# Main_Roll.net
KiCad netlist of a schematic drawn in Altium Designer
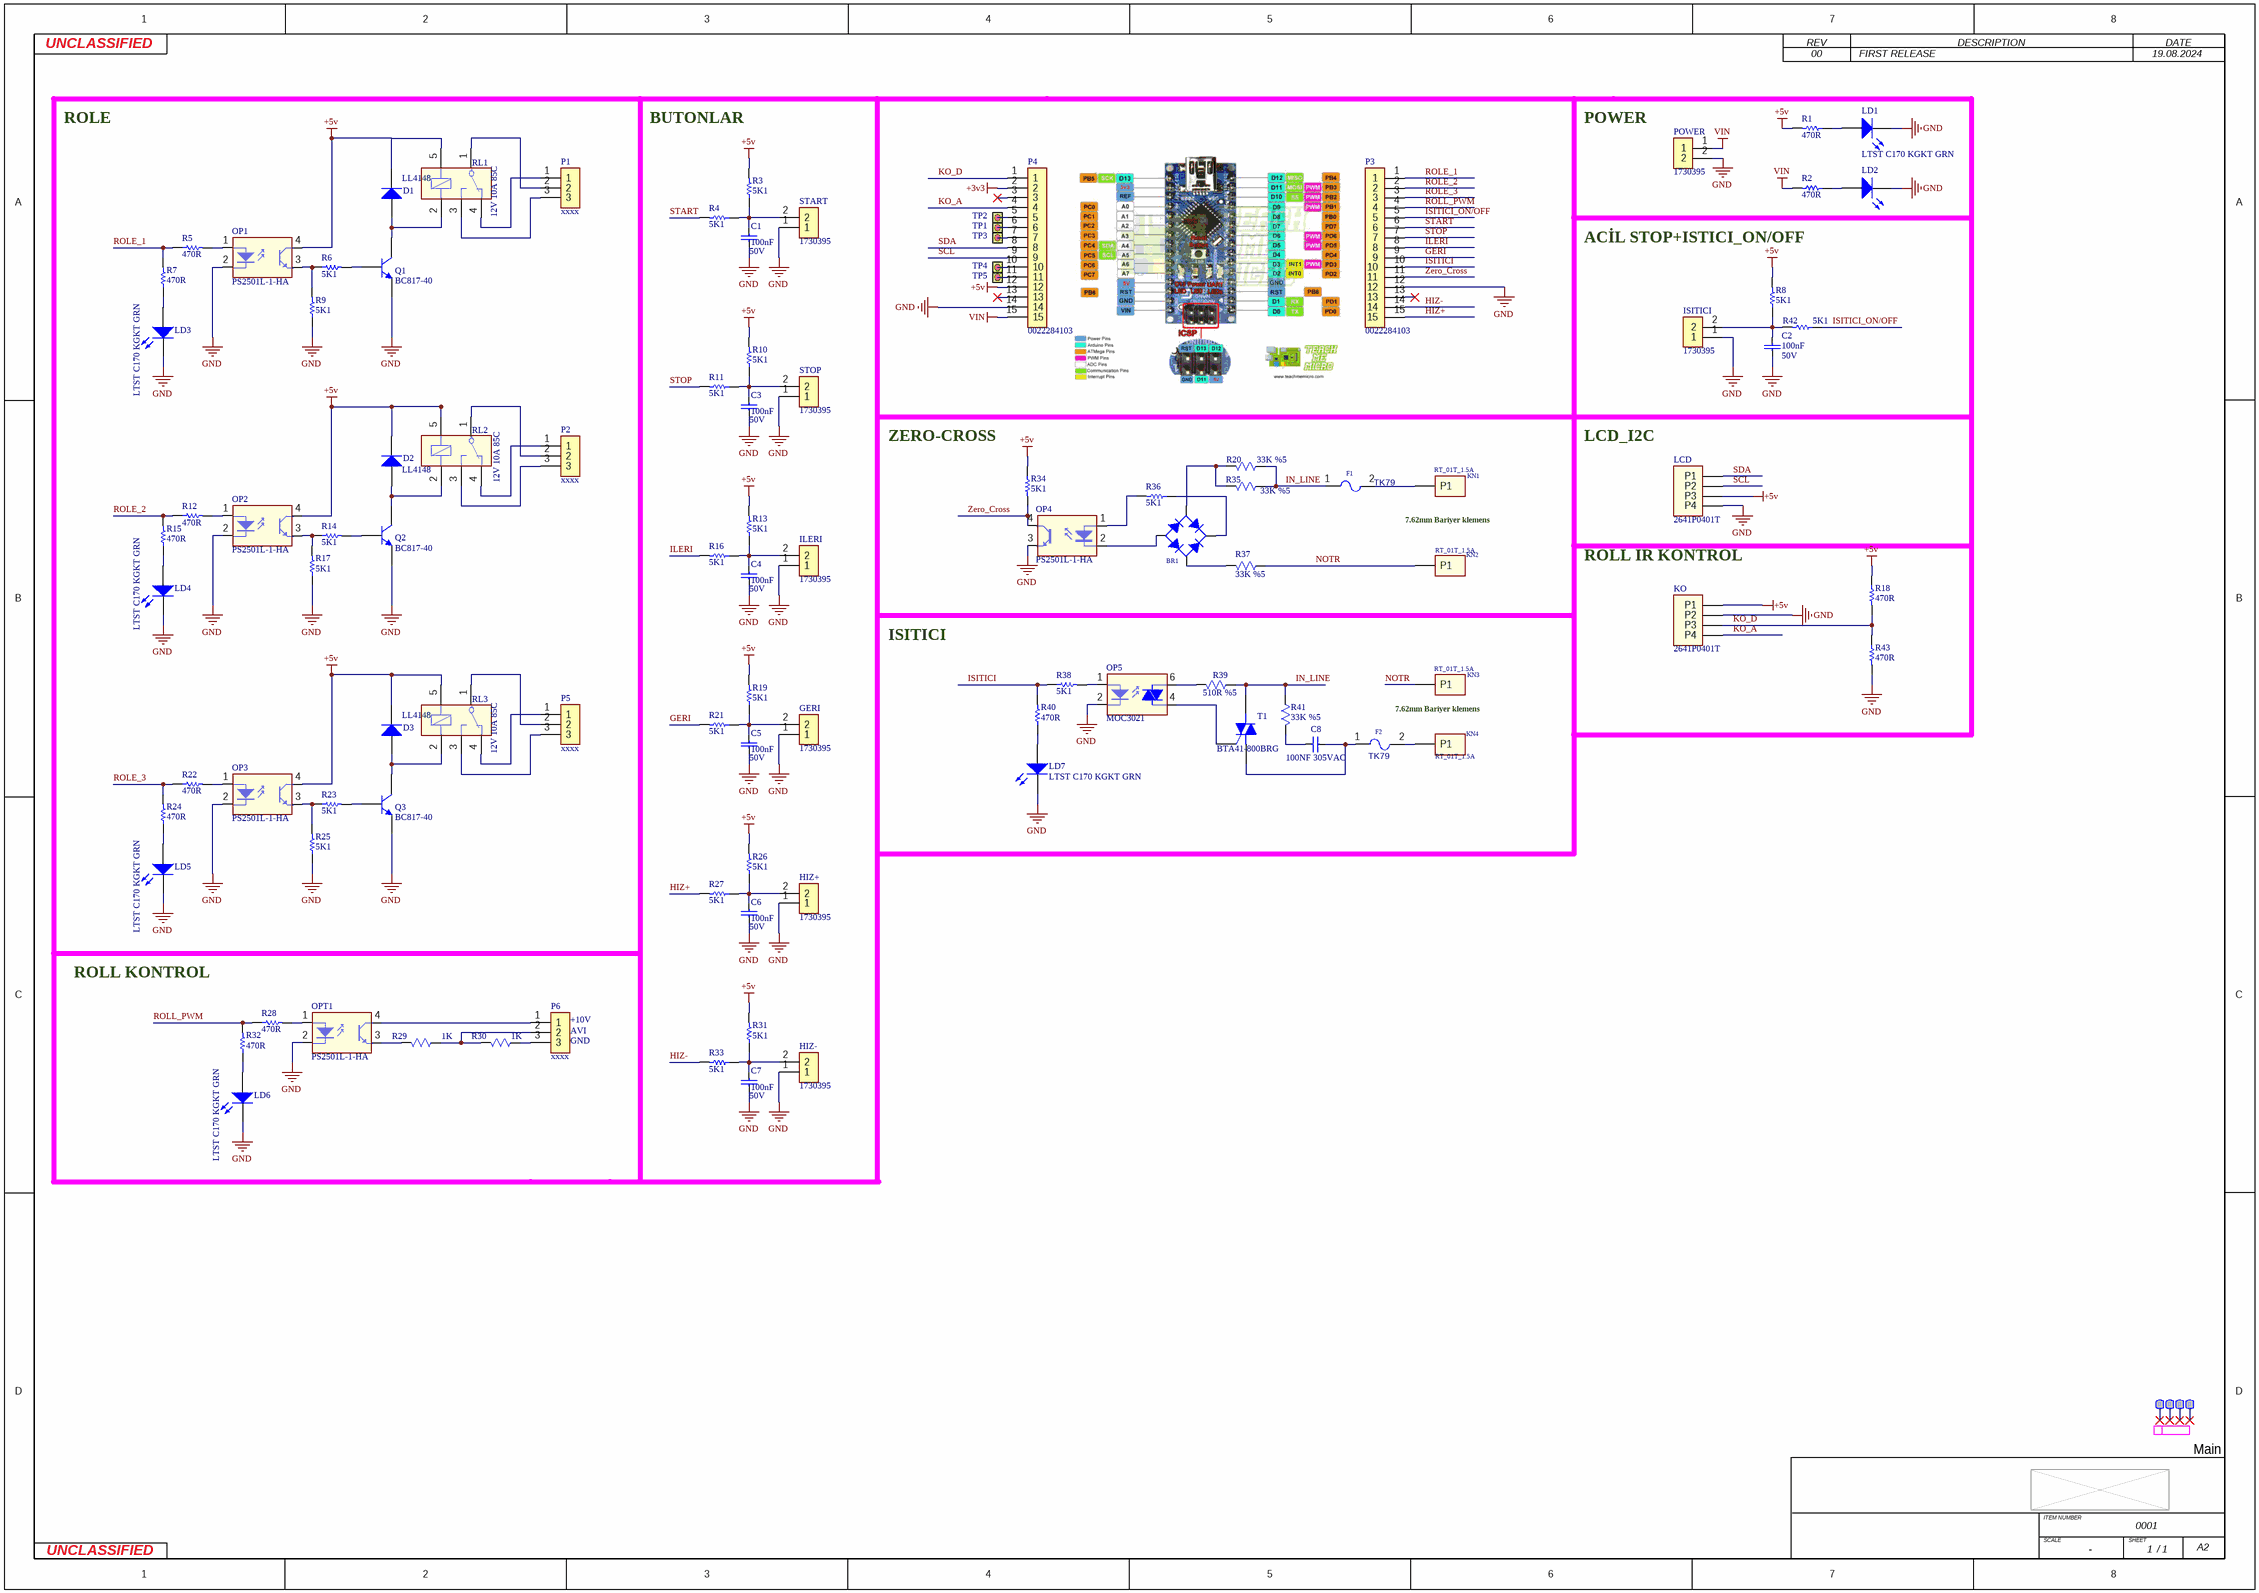
[diagram p0: Main_Roll.SchDoc]

(export (version "E")
  (design (tool "Eeschema 10.0.6"))
  (components
    (comp (ref "BR1")
      (value "~")
      (footprint "TO-269AA")
      (fields (field (name "PART NUMBER") "MB6S"))
      (libsource (lib "A_LIB") (part "B250D"))
    )
    (comp (ref "C1")
      (value "100nF")
      (footprint "C1206")
      (description "CAPACITOR, CERAMIC, 100nF, 50V, 10% TOLERANCE, X7R, 1206 PACKAGE")
      (fields
        (field (name "INITIAL VOLTAGE") "50V")
        (field (name "MANUFACTURER") "AVX")
        (field (name "TOLERANCE") "10%")
      )
      (libsource (lib "R_DB_LIB") (part "CAP"))
    )
    (comp (ref "C2")
      (value "100nF")
      (footprint "C1206")
      (description "CAPACITOR, CERAMIC, 100nF, 50V, 10% TOLERANCE, X7R, 1206 PACKAGE")
      (fields
        (field (name "INITIAL VOLTAGE") "50V")
        (field (name "MANUFACTURER") "AVX")
        (field (name "TOLERANCE") "10%")
      )
      (libsource (lib "R_DB_LIB") (part "CAP"))
    )
    (comp (ref "C3")
      (value "100nF")
      (footprint "C1206")
      (description "CAPACITOR, CERAMIC, 100nF, 50V, 10% TOLERANCE, X7R, 1206 PACKAGE")
      (fields
        (field (name "INITIAL VOLTAGE") "50V")
        (field (name "MANUFACTURER") "AVX")
        (field (name "TOLERANCE") "10%")
      )
      (libsource (lib "R_DB_LIB") (part "CAP"))
    )
    (comp (ref "C4")
      (value "100nF")
      (footprint "C1206")
      (description "CAPACITOR, CERAMIC, 100nF, 50V, 10% TOLERANCE, X7R, 1206 PACKAGE")
      (fields
        (field (name "INITIAL VOLTAGE") "50V")
        (field (name "MANUFACTURER") "AVX")
        (field (name "TOLERANCE") "10%")
      )
      (libsource (lib "R_DB_LIB") (part "CAP"))
    )
    (comp (ref "C5")
      (value "100nF")
      (footprint "C1206")
      (description "CAPACITOR, CERAMIC, 100nF, 50V, 10% TOLERANCE, X7R, 1206 PACKAGE")
      (fields
        (field (name "INITIAL VOLTAGE") "50V")
        (field (name "MANUFACTURER") "AVX")
        (field (name "TOLERANCE") "10%")
      )
      (libsource (lib "R_DB_LIB") (part "CAP"))
    )
    (comp (ref "C6")
      (value "100nF")
      (footprint "C1206")
      (description "CAPACITOR, CERAMIC, 100nF, 50V, 10% TOLERANCE, X7R, 1206 PACKAGE")
      (fields
        (field (name "INITIAL VOLTAGE") "50V")
        (field (name "MANUFACTURER") "AVX")
        (field (name "TOLERANCE") "10%")
      )
      (libsource (lib "R_DB_LIB") (part "CAP"))
    )
    (comp (ref "C7")
      (value "100nF")
      (footprint "C1206")
      (description "CAPACITOR, CERAMIC, 100nF, 50V, 10% TOLERANCE, X7R, 1206 PACKAGE")
      (fields
        (field (name "INITIAL VOLTAGE") "50V")
        (field (name "MANUFACTURER") "AVX")
        (field (name "TOLERANCE") "10%")
      )
      (libsource (lib "R_DB_LIB") (part "CAP"))
    )
    (comp (ref "C8")
      (value "100NF 305VAC")
      (footprint "CFR F15 L18 B6 H12")
      (fields (field (name "PART NUMBER") "CFR15 100NF 305VAC M85 X2"))
      (libsource (lib "A_LIB") (part "Capacitor"))
    )
    (comp (ref "D1")
      (value "LL4148")
      (footprint "SOD80")
      (fields (field (name "PART NUMBER") "1N4148-S"))
      (libsource (lib "A_LIB") (part "Diode"))
    )
    (comp (ref "D2")
      (value "LL4148")
      (footprint "SOD80")
      (fields (field (name "PART NUMBER") "1N4148-S"))
      (libsource (lib "") (part "Diode_1"))
    )
    (comp (ref "D3")
      (value "LL4148")
      (footprint "SOD80")
      (fields (field (name "PART NUMBER") "1N4148-S"))
      (libsource (lib "A_LIB") (part "Diode"))
    )
    (comp (ref "ETİKET1") (value "Etiket") (footprint "ETIKET") (libsource (lib "R_DB_LIB") (part "Etiket")))
    (comp (ref "F1")
      (value "TK79")
      (footprint "TK 79")
      (fields (field (name "PART NUMBER") "FUSE TK79"))
      (libsource (lib "A_LIB") (part "Fuse"))
    )
    (comp (ref "F2")
      (value "TK79")
      (footprint "TK 79")
      (fields (field (name "PART NUMBER") "FUSE TK79"))
      (libsource (lib "") (part "Fuse_1"))
    )
    (comp (ref "GERI")
      (value "1730395")
      (footprint "1730395")
      (description "CONN,RECT,PLUG,5.08MM,1ROW,2P-TH,1730395")
      (fields (field (name "MANUFACTURER") "PHONEIX CONTACT"))
      (libsource (lib "") (part "HDR1X2_1"))
    )
    (comp (ref "HIZ+")
      (value "1730395")
      (footprint "1730395")
      (description "CONN,RECT,PLUG,5.08MM,1ROW,2P-TH,1730395")
      (fields (field (name "MANUFACTURER") "PHONEIX CONTACT"))
      (libsource (lib "") (part "HDR1X2_1"))
    )
    (comp (ref "HIZ-")
      (value "1730395")
      (footprint "1730395")
      (description "CONN,RECT,PLUG,5.08MM,1ROW,2P-TH,1730395")
      (fields (field (name "MANUFACTURER") "PHONEIX CONTACT"))
      (libsource (lib "") (part "HDR1X2_1"))
    )
    (comp (ref "ILERI")
      (value "1730395")
      (footprint "1730395")
      (description "CONN,RECT,PLUG,5.08MM,1ROW,2P-TH,1730395")
      (fields (field (name "MANUFACTURER") "PHONEIX CONTACT"))
      (libsource (lib "") (part "HDR1X2_1"))
    )
    (comp (ref "ISITICI")
      (value "1730395")
      (footprint "1730395")
      (description "CONN,RECT,PLUG,5.08MM,1ROW,2P-TH,1730395")
      (fields (field (name "MANUFACTURER") "PHONEIX CONTACT"))
      (libsource (lib "R_DB_LIB") (part "HDR1X2"))
    )
    (comp (ref "KN1")
      (value "RT_01T_1.5A")
      (footprint "RT_01T_1.5A")
      (libsource (lib "A_LIB") (part "CONN 1_1"))
    )
    (comp (ref "KN2")
      (value "RT_01T_1.5A")
      (footprint "RT_01T_1.5A")
      (libsource (lib "A_LIB") (part "CONN 1_1"))
    )
    (comp (ref "KN3")
      (value "RT_01T_1.5A")
      (footprint "RT_01T_1.5A")
      (libsource (lib "A_LIB") (part "CONN 1_1"))
    )
    (comp (ref "KN4")
      (value "RT_01T_1.5A")
      (footprint "RT_01T_1.5A")
      (libsource (lib "A_LIB") (part "CONN 1_1"))
    )
    (comp (ref "KO") (value "2641P0401T") (footprint "35312_4") (libsource (lib "A_LIB") (part "CONN 4")))
    (comp (ref "LCD") (value "2641P0401T") (footprint "35312_4") (libsource (lib "A_LIB") (part "CONN 4")))
    (comp (ref "LD1")
      (value "LTST C170 KGKT GRN")
      (footprint "LED0805 GRN")
      (libsource (lib "A_LIB") (part "LED"))
    )
    (comp (ref "LD2")
      (value "LTST C170 KGKT GRN")
      (footprint "LED0805 GRN")
      (libsource (lib "A_LIB") (part "LED"))
    )
    (comp (ref "LD3")
      (value "LTST C170 KGKT GRN")
      (footprint "LED0805 GRN")
      (libsource (lib "A_LIB") (part "LED"))
    )
    (comp (ref "LD4")
      (value "LTST C170 KGKT GRN")
      (footprint "LED0805 GRN")
      (libsource (lib "A_LIB") (part "LED"))
    )
    (comp (ref "LD5")
      (value "LTST C170 KGKT GRN")
      (footprint "LED0805 GRN")
      (libsource (lib "A_LIB") (part "LED"))
    )
    (comp (ref "LD6")
      (value "LTST C170 KGKT GRN")
      (footprint "LED0805 GRN")
      (libsource (lib "A_LIB") (part "LED"))
    )
    (comp (ref "LD7")
      (value "LTST C170 KGKT GRN")
      (footprint "LED0805 GRN")
      (libsource (lib "") (part "LED_1"))
    )
    (comp (ref "OP1")
      (value "PS2501L-1-HA")
      (footprint "DIP4SMD")
      (fields (field (name "PART NUMBER") "PS2501-1-H"))
      (libsource (lib "") (part "Optocoupler(AKEC)_1"))
    )
    (comp (ref "OP2")
      (value "PS2501L-1-HA")
      (footprint "DIP4SMD")
      (fields (field (name "PART NUMBER") "PS2501-1-H"))
      (libsource (lib "") (part "Optocoupler(AKEC)_1"))
    )
    (comp (ref "OP3")
      (value "PS2501L-1-HA")
      (footprint "DIP4SMD")
      (fields (field (name "PART NUMBER") "PS2501-1-H"))
      (libsource (lib "") (part "Optocoupler(AKEC)_1"))
    )
    (comp (ref "OP4")
      (value "PS2501L-1-HA")
      (footprint "DIP4SMD")
      (fields (field (name "PART NUMBER") "PS2501-1-H"))
      (libsource (lib "A_LIB") (part "Optocoupler(AKEC)"))
    )
    (comp (ref "OP5") (value "MOC3021") (footprint "DIP6") (libsource (lib "A_LIB") (part "Optotriac")))
    (comp (ref "OPT1")
      (value "PS2501L-1-HA")
      (footprint "DIP4SMD")
      (fields (field (name "PART NUMBER") "PS2501-1-H"))
      (libsource (lib "") (part "Optocoupler(AKEC)_1"))
    )
    (comp (ref "P1")
      (value "xxxx")
      (footprint "5.08_3pin")
      (description "CONN,RECT,PLUG,5.08MM,1ROW,3P-TH,xxx")
      (fields (field (name "MANUFACTURER") "PHONEIX CONTACT"))
      (libsource (lib "R_DB_LIB") (part "HDR1X3"))
    )
    (comp (ref "P2")
      (value "xxxx")
      (footprint "5.08_3pin")
      (description "CONN,RECT,PLUG,5.08MM,1ROW,3P-TH,xxx")
      (fields (field (name "MANUFACTURER") "PHONEIX CONTACT"))
      (libsource (lib "R_DB_LIB") (part "HDR1X3"))
    )
    (comp (ref "P3")
      (value "0022284103")
      (footprint "HDR1X15")
      (description "CONN, 2.54MM PITCH, THROUGH HOLE, SINGLE ROW, VERTICAL, 15 PIN, PIN,")
      (fields
        (field (name "MANUFACTURER") "MOLEX")
        (field (name "HELPURL") "‪D:\\Datasheets\\ssw\\ssw-1xx-xx-xxx-x-xx-xxx-xx-mkt.pdf")
      )
      (libsource (lib "R_DB_LIB") (part "HDR1X15"))
    )
    (comp (ref "P4")
      (value "0022284103")
      (footprint "HDR1X15")
      (description "CONN, 2.54MM PITCH, THROUGH HOLE, SINGLE ROW, VERTICAL, 15 PIN, PIN,")
      (fields
        (field (name "MANUFACTURER") "MOLEX")
        (field (name "HELPURL") "‪D:\\Datasheets\\ssw\\ssw-1xx-xx-xxx-x-xx-xxx-xx-mkt.pdf")
      )
      (libsource (lib "") (part "HDR1X15_1"))
    )
    (comp (ref "P5")
      (value "xxxx")
      (footprint "5.08_3pin")
      (description "CONN,RECT,PLUG,5.08MM,1ROW,3P-TH,xxx")
      (fields (field (name "MANUFACTURER") "PHONEIX CONTACT"))
      (libsource (lib "R_DB_LIB") (part "HDR1X3"))
    )
    (comp (ref "P6")
      (value "xxxx")
      (footprint "5.08_3pin")
      (description "CONN,RECT,PLUG,5.08MM,1ROW,3P-TH,xxx")
      (fields (field (name "MANUFACTURER") "PHONEIX CONTACT"))
      (libsource (lib "R_DB_LIB") (part "HDR1X3"))
    )
    (comp (ref "POWER")
      (value "1730395")
      (footprint "1730395")
      (description "CONN,RECT,PLUG,5.08MM,1ROW,2P-TH,1730395")
      (fields (field (name "MANUFACTURER") "PHONEIX CONTACT"))
      (libsource (lib "") (part "HDR1X2_2"))
    )
    (comp (ref "Q1") (value "BC817-40") (footprint "SOT23") (libsource (lib "A_LIB") (part "NPN(BEC)")))
    (comp (ref "Q2") (value "BC817-40") (footprint "SOT23") (libsource (lib "") (part "NPN(BEC)_1")))
    (comp (ref "Q3") (value "BC817-40") (footprint "SOT23") (libsource (lib "A_LIB") (part "NPN(BEC)")))
    (comp (ref "R1")
      (value "470R")
      (footprint "R1206")
      (description "RESISTOR , 470R, 0.25W, 1%, 1206 PACKAGE")
      (fields (field (name "MANUFACTURER") "MULTICOMP") (field (name "TOLERANCE") "1%"))
      (libsource (lib "R_DB_LIB") (part "Resistor"))
    )
    (comp (ref "R2")
      (value "470R")
      (footprint "R1206")
      (description "RESISTOR , 470R, 0.25W, 1%, 1206 PACKAGE")
      (fields (field (name "MANUFACTURER") "MULTICOMP") (field (name "TOLERANCE") "1%"))
      (libsource (lib "R_DB_LIB") (part "Resistor"))
    )
    (comp (ref "R3")
      (value "5K1")
      (footprint "R1206")
      (description "RESISTOR , 5K1, 1/4W, 1%, 1206 PACKAGE")
      (fields (field (name "MANUFACTURER") "ROYALOHM") (field (name "TOLERANCE") "1%"))
      (libsource (lib "R_DB_LIB") (part "Resistor"))
    )
    (comp (ref "R4")
      (value "5K1")
      (footprint "R1206")
      (description "RESISTOR , 5K1, 1/4W, 1%, 1206 PACKAGE")
      (fields (field (name "MANUFACTURER") "ROYALOHM") (field (name "TOLERANCE") "1%"))
      (libsource (lib "R_DB_LIB") (part "Resistor"))
    )
    (comp (ref "R5")
      (value "470R")
      (footprint "R1206")
      (description "RESISTOR , 470R, 0.25W, 1%, 1206 PACKAGE")
      (fields (field (name "MANUFACTURER") "MULTICOMP") (field (name "TOLERANCE") "1%"))
      (libsource (lib "R_DB_LIB") (part "Resistor"))
    )
    (comp (ref "R6")
      (value "5K1")
      (footprint "R1206")
      (description "RESISTOR , 5K1, 1/4W, 1%, 1206 PACKAGE")
      (fields (field (name "MANUFACTURER") "ROYALOHM") (field (name "TOLERANCE") "1%"))
      (libsource (lib "R_DB_LIB") (part "Resistor"))
    )
    (comp (ref "R7")
      (value "470R")
      (footprint "R1206")
      (description "RESISTOR , 470R, 0.25W, 1%, 1206 PACKAGE")
      (fields (field (name "MANUFACTURER") "MULTICOMP") (field (name "TOLERANCE") "1%"))
      (libsource (lib "R_DB_LIB") (part "Resistor"))
    )
    (comp (ref "R8")
      (value "5K1")
      (footprint "R1206")
      (description "RESISTOR , 5K1, 1/4W, 1%, 1206 PACKAGE")
      (fields (field (name "MANUFACTURER") "ROYALOHM") (field (name "TOLERANCE") "1%"))
      (libsource (lib "R_DB_LIB") (part "Resistor"))
    )
    (comp (ref "R9")
      (value "5K1")
      (footprint "R1206")
      (description "RESISTOR , 5K1, 1/4W, 1%, 1206 PACKAGE")
      (fields (field (name "MANUFACTURER") "ROYALOHM") (field (name "TOLERANCE") "1%"))
      (libsource (lib "R_DB_LIB") (part "Resistor"))
    )
    (comp (ref "R10")
      (value "5K1")
      (footprint "R1206")
      (description "RESISTOR , 5K1, 1/4W, 1%, 1206 PACKAGE")
      (fields (field (name "MANUFACTURER") "ROYALOHM") (field (name "TOLERANCE") "1%"))
      (libsource (lib "R_DB_LIB") (part "Resistor"))
    )
    (comp (ref "R11")
      (value "5K1")
      (footprint "R1206")
      (description "RESISTOR , 5K1, 1/4W, 1%, 1206 PACKAGE")
      (fields (field (name "MANUFACTURER") "ROYALOHM") (field (name "TOLERANCE") "1%"))
      (libsource (lib "R_DB_LIB") (part "Resistor"))
    )
    (comp (ref "R12")
      (value "470R")
      (footprint "R1206")
      (description "RESISTOR , 470R, 0.25W, 1%, 1206 PACKAGE")
      (fields (field (name "MANUFACTURER") "MULTICOMP") (field (name "TOLERANCE") "1%"))
      (libsource (lib "R_DB_LIB") (part "Resistor"))
    )
    (comp (ref "R13")
      (value "5K1")
      (footprint "R1206")
      (description "RESISTOR , 5K1, 1/4W, 1%, 1206 PACKAGE")
      (fields (field (name "MANUFACTURER") "ROYALOHM") (field (name "TOLERANCE") "1%"))
      (libsource (lib "R_DB_LIB") (part "Resistor"))
    )
    (comp (ref "R14")
      (value "5K1")
      (footprint "R1206")
      (description "RESISTOR , 5K1, 1/4W, 1%, 1206 PACKAGE")
      (fields (field (name "MANUFACTURER") "ROYALOHM") (field (name "TOLERANCE") "1%"))
      (libsource (lib "R_DB_LIB") (part "Resistor"))
    )
    (comp (ref "R15")
      (value "470R")
      (footprint "R1206")
      (description "RESISTOR , 470R, 0.25W, 1%, 1206 PACKAGE")
      (fields (field (name "MANUFACTURER") "MULTICOMP") (field (name "TOLERANCE") "1%"))
      (libsource (lib "R_DB_LIB") (part "Resistor"))
    )
    (comp (ref "R16")
      (value "5K1")
      (footprint "R1206")
      (description "RESISTOR , 5K1, 1/4W, 1%, 1206 PACKAGE")
      (fields (field (name "MANUFACTURER") "ROYALOHM") (field (name "TOLERANCE") "1%"))
      (libsource (lib "R_DB_LIB") (part "Resistor"))
    )
    (comp (ref "R17")
      (value "5K1")
      (footprint "R1206")
      (description "RESISTOR , 5K1, 1/4W, 1%, 1206 PACKAGE")
      (fields (field (name "MANUFACTURER") "ROYALOHM") (field (name "TOLERANCE") "1%"))
      (libsource (lib "R_DB_LIB") (part "Resistor"))
    )
    (comp (ref "R18")
      (value "470R")
      (footprint "R1206")
      (description "RESISTOR , 470R, 0.25W, 1%, 1206 PACKAGE")
      (fields (field (name "MANUFACTURER") "MULTICOMP") (field (name "TOLERANCE") "1%"))
      (libsource (lib "R_DB_LIB") (part "Resistor"))
    )
    (comp (ref "R19")
      (value "5K1")
      (footprint "R1206")
      (description "RESISTOR , 5K1, 1/4W, 1%, 1206 PACKAGE")
      (fields (field (name "MANUFACTURER") "ROYALOHM") (field (name "TOLERANCE") "1%"))
      (libsource (lib "R_DB_LIB") (part "Resistor"))
    )
    (comp (ref "R20")
      (value "33K %5")
      (footprint "RCA0516")
      (fields (field (name "PART NUMBER") "RCA0516 33K %5 2W SS"))
      (libsource (lib "A_LIB") (part "Resistor"))
    )
    (comp (ref "R21")
      (value "5K1")
      (footprint "R1206")
      (description "RESISTOR , 5K1, 1/4W, 1%, 1206 PACKAGE")
      (fields (field (name "MANUFACTURER") "ROYALOHM") (field (name "TOLERANCE") "1%"))
      (libsource (lib "R_DB_LIB") (part "Resistor"))
    )
    (comp (ref "R22")
      (value "470R")
      (footprint "R1206")
      (description "RESISTOR , 470R, 0.25W, 1%, 1206 PACKAGE")
      (fields (field (name "MANUFACTURER") "MULTICOMP") (field (name "TOLERANCE") "1%"))
      (libsource (lib "R_DB_LIB") (part "Resistor"))
    )
    (comp (ref "R23")
      (value "5K1")
      (footprint "R1206")
      (description "RESISTOR , 5K1, 1/4W, 1%, 1206 PACKAGE")
      (fields (field (name "MANUFACTURER") "ROYALOHM") (field (name "TOLERANCE") "1%"))
      (libsource (lib "R_DB_LIB") (part "Resistor"))
    )
    (comp (ref "R24")
      (value "470R")
      (footprint "R1206")
      (description "RESISTOR , 470R, 0.25W, 1%, 1206 PACKAGE")
      (fields (field (name "MANUFACTURER") "MULTICOMP") (field (name "TOLERANCE") "1%"))
      (libsource (lib "R_DB_LIB") (part "Resistor"))
    )
    (comp (ref "R25")
      (value "5K1")
      (footprint "R1206")
      (description "RESISTOR , 5K1, 1/4W, 1%, 1206 PACKAGE")
      (fields (field (name "MANUFACTURER") "ROYALOHM") (field (name "TOLERANCE") "1%"))
      (libsource (lib "R_DB_LIB") (part "Resistor"))
    )
    (comp (ref "R26")
      (value "5K1")
      (footprint "R1206")
      (description "RESISTOR , 5K1, 1/4W, 1%, 1206 PACKAGE")
      (fields (field (name "MANUFACTURER") "ROYALOHM") (field (name "TOLERANCE") "1%"))
      (libsource (lib "R_DB_LIB") (part "Resistor"))
    )
    (comp (ref "R27")
      (value "5K1")
      (footprint "R1206")
      (description "RESISTOR , 5K1, 1/4W, 1%, 1206 PACKAGE")
      (fields (field (name "MANUFACTURER") "ROYALOHM") (field (name "TOLERANCE") "1%"))
      (libsource (lib "R_DB_LIB") (part "Resistor"))
    )
    (comp (ref "R28")
      (value "470R")
      (footprint "R1206")
      (description "RESISTOR , 470R, 0.25W, 1%, 1206 PACKAGE")
      (fields (field (name "MANUFACTURER") "MULTICOMP") (field (name "TOLERANCE") "1%"))
      (libsource (lib "R_DB_LIB") (part "Resistor"))
    )
    (comp (ref "R29")
      (value "33K %5")
      (footprint "RCA0516")
      (fields (field (name "PART NUMBER") "RCA0516 33K %5 2W SS"))
      (libsource (lib "A_LIB") (part "Resistor"))
    )
    (comp (ref "R30")
      (value "33K %5")
      (footprint "RCA0516")
      (fields (field (name "PART NUMBER") "RCA0516 33K %5 2W SS"))
      (libsource (lib "A_LIB") (part "Resistor"))
    )
    (comp (ref "R31")
      (value "5K1")
      (footprint "R1206")
      (description "RESISTOR , 5K1, 1/4W, 1%, 1206 PACKAGE")
      (fields (field (name "MANUFACTURER") "ROYALOHM") (field (name "TOLERANCE") "1%"))
      (libsource (lib "R_DB_LIB") (part "Resistor"))
    )
    (comp (ref "R32")
      (value "470R")
      (footprint "R1206")
      (description "RESISTOR , 470R, 0.25W, 1%, 1206 PACKAGE")
      (fields (field (name "MANUFACTURER") "MULTICOMP") (field (name "TOLERANCE") "1%"))
      (libsource (lib "R_DB_LIB") (part "Resistor"))
    )
    (comp (ref "R33")
      (value "5K1")
      (footprint "R1206")
      (description "RESISTOR , 5K1, 1/4W, 1%, 1206 PACKAGE")
      (fields (field (name "MANUFACTURER") "ROYALOHM") (field (name "TOLERANCE") "1%"))
      (libsource (lib "R_DB_LIB") (part "Resistor"))
    )
    (comp (ref "R34")
      (value "5K1")
      (footprint "R1206")
      (description "RESISTOR , 5K1, 1/4W, 1%, 1206 PACKAGE")
      (fields (field (name "MANUFACTURER") "ROYALOHM") (field (name "TOLERANCE") "1%"))
      (libsource (lib "R_DB_LIB") (part "Resistor"))
    )
    (comp (ref "R35")
      (value "33K %5")
      (footprint "RCA0516")
      (fields (field (name "PART NUMBER") "RCA0516 33K %5 2W SS"))
      (libsource (lib "A_LIB") (part "Resistor"))
    )
    (comp (ref "R36")
      (value "5K1")
      (footprint "R1206")
      (description "RESISTOR , 5K1, 1/4W, 1%, 1206 PACKAGE")
      (fields (field (name "MANUFACTURER") "ROYALOHM") (field (name "TOLERANCE") "1%"))
      (libsource (lib "R_DB_LIB") (part "Resistor"))
    )
    (comp (ref "R37")
      (value "33K %5")
      (footprint "RCA0516")
      (fields (field (name "PART NUMBER") "RCA0516 33K %5 2W SS"))
      (libsource (lib "A_LIB") (part "Resistor"))
    )
    (comp (ref "R38")
      (value "5K1")
      (footprint "R1206")
      (description "RESISTOR , 5K1, 1/4W, 1%, 1206 PACKAGE")
      (fields (field (name "MANUFACTURER") "ROYALOHM") (field (name "TOLERANCE") "1%"))
      (libsource (lib "R_DB_LIB") (part "Resistor"))
    )
    (comp (ref "R39")
      (value "510R %5")
      (footprint "RCA0411")
      (fields (field (name "PART NUMBER") "RCA0411 510R %5 1W"))
      (libsource (lib "A_LIB") (part "Resistor"))
    )
    (comp (ref "R40")
      (value "470R")
      (footprint "R1206")
      (description "RESISTOR , 470R, 0.25W, 1%, 1206 PACKAGE")
      (fields (field (name "MANUFACTURER") "MULTICOMP") (field (name "TOLERANCE") "1%"))
      (libsource (lib "R_DB_LIB") (part "Resistor"))
    )
    (comp (ref "R41")
      (value "33K %5")
      (footprint "RCA0516")
      (fields (field (name "PART NUMBER") "RCA0516 33K %5 2W SS"))
      (libsource (lib "A_LIB") (part "Resistor"))
    )
    (comp (ref "R42")
      (value "5K1")
      (footprint "R1206")
      (description "RESISTOR , 5K1, 1/4W, 1%, 1206 PACKAGE")
      (fields (field (name "MANUFACTURER") "ROYALOHM") (field (name "TOLERANCE") "1%"))
      (libsource (lib "R_DB_LIB") (part "Resistor"))
    )
    (comp (ref "R43")
      (value "470R")
      (footprint "R1206")
      (description "RESISTOR , 470R, 0.25W, 1%, 1206 PACKAGE")
      (fields (field (name "MANUFACTURER") "MULTICOMP") (field (name "TOLERANCE") "1%"))
      (libsource (lib "R_DB_LIB") (part "Resistor"))
    )
    (comp (ref "RL1")
      (value "12V 10A 85C")
      (footprint "JS1")
      (fields (field (name "PART NUMBER") "JS1 B 12V 10A 85C"))
      (libsource (lib "A_LIB") (part "JS1"))
    )
    (comp (ref "RL2")
      (value "12V 10A 85C")
      (footprint "JS1")
      (fields (field (name "PART NUMBER") "JS1 B 12V 10A 85C"))
      (libsource (lib "") (part "JS1_1"))
    )
    (comp (ref "RL3")
      (value "12V 10A 85C")
      (footprint "JS1")
      (fields (field (name "PART NUMBER") "JS1 B 12V 10A 85C"))
      (libsource (lib "A_LIB") (part "JS1"))
    )
    (comp (ref "START")
      (value "1730395")
      (footprint "1730395")
      (description "CONN,RECT,PLUG,5.08MM,1ROW,2P-TH,1730395")
      (fields (field (name "MANUFACTURER") "PHONEIX CONTACT"))
      (libsource (lib "") (part "HDR1X2_1"))
    )
    (comp (ref "STOP")
      (value "1730395")
      (footprint "1730395")
      (description "CONN,RECT,PLUG,5.08MM,1ROW,2P-TH,1730395")
      (fields (field (name "MANUFACTURER") "PHONEIX CONTACT"))
      (libsource (lib "") (part "HDR1X2_1"))
    )
    (comp (ref "T1")
      (value "BTA41-800BRG")
      (footprint "TO247AC")
      (description "BTA41")
      (fields (field (name "MANUFACTURER") "STMicroelectronics"))
      (libsource (lib "R_DB_LIB") (part "TRIAC"))
    )
    (comp (ref "TP1")
      (value "Test Point")
      (footprint "TESTPIN")
      (fields (field (name "PART NUMBER") "TESTPIN"))
      (libsource (lib "A_LIB") (part "Test Point"))
    )
    (comp (ref "TP2")
      (value "Test Point")
      (footprint "TESTPIN")
      (fields (field (name "PART NUMBER") "TESTPIN"))
      (libsource (lib "A_LIB") (part "Test Point"))
    )
    (comp (ref "TP3")
      (value "Test Point")
      (footprint "TESTPIN")
      (fields (field (name "PART NUMBER") "TESTPIN"))
      (libsource (lib "A_LIB") (part "Test Point"))
    )
    (comp (ref "TP4")
      (value "Test Point")
      (footprint "TESTPIN")
      (fields (field (name "PART NUMBER") "TESTPIN"))
      (libsource (lib "A_LIB") (part "Test Point"))
    )
    (comp (ref "TP5")
      (value "Test Point")
      (footprint "TESTPIN")
      (fields (field (name "PART NUMBER") "TESTPIN"))
      (libsource (lib "A_LIB") (part "Test Point"))
    )
    (comp (ref "VD1")
      (value "Vida 3mm")
      (footprint "Vida 3mm")
      (libsource (lib "R_DB_LIB") (part "Vida 3mm"))
    )
    (comp (ref "VD2")
      (value "Vida 3mm")
      (footprint "Vida 3mm")
      (libsource (lib "R_DB_LIB") (part "Vida 3mm"))
    )
    (comp (ref "VD3")
      (value "Vida 3mm")
      (footprint "Vida 3mm")
      (libsource (lib "R_DB_LIB") (part "Vida 3mm"))
    )
    (comp (ref "VD4")
      (value "Vida 3mm")
      (footprint "Vida 3mm")
      (libsource (lib "R_DB_LIB") (part "Vida 3mm"))
    )
  )
  (nets
    (net (code "1") (name "+3v3") (class "Default")
      (node (ref "P4") (pin "2") (pinfunction "2_2") (pintype "passive"))
    )
    (net (code "2") (name "+5v") (class "Default")
      (node (ref "D1") (pin "1") (pinfunction "K_1") (pintype "passive"))
      (node (ref "D2") (pin "1") (pinfunction "K_1") (pintype "passive"))
      (node (ref "D3") (pin "1") (pinfunction "K_1") (pintype "passive"))
      (node (ref "KO") (pin "1") (pinfunction "P1_1") (pintype "passive"))
      (node (ref "LCD") (pin "3") (pinfunction "P3_3") (pintype "passive"))
      (node (ref "OP1") (pin "4") (pinfunction "C_4") (pintype "passive"))
      (node (ref "OP2") (pin "4") (pinfunction "C_4") (pintype "passive"))
      (node (ref "OP3") (pin "4") (pinfunction "C_4") (pintype "passive"))
      (node (ref "P4") (pin "12") (pinfunction "12_12") (pintype "passive"))
      (node (ref "R1") (pin "2") (pinfunction "2_2") (pintype "passive"))
      (node (ref "R10") (pin "2") (pinfunction "2_2") (pintype "passive"))
      (node (ref "R13") (pin "2") (pinfunction "2_2") (pintype "passive"))
      (node (ref "R18") (pin "1") (pinfunction "1_1") (pintype "passive"))
      (node (ref "R19") (pin "2") (pinfunction "2_2") (pintype "passive"))
      (node (ref "R26") (pin "2") (pinfunction "2_2") (pintype "passive"))
      (node (ref "R3") (pin "2") (pinfunction "2_2") (pintype "passive"))
      (node (ref "R31") (pin "2") (pinfunction "2_2") (pintype "passive"))
      (node (ref "R34") (pin "1") (pinfunction "1_1") (pintype "passive"))
      (node (ref "R8") (pin "2") (pinfunction "2_2") (pintype "passive"))
      (node (ref "RL1") (pin "5") (pinfunction "L2_5") (pintype "passive"))
      (node (ref "RL2") (pin "5") (pinfunction "L2_5") (pintype "passive"))
      (node (ref "RL3") (pin "5") (pinfunction "L2_5") (pintype "passive"))
    )
    (net (code "3") (name "/GERI") (class "Default")
      (node (ref "P3") (pin "9") (pinfunction "9_9") (pintype "passive"))
      (node (ref "R21") (pin "2") (pinfunction "2_2") (pintype "passive"))
    )
    (net (code "4") (name "/HIZ+") (class "Default")
      (node (ref "P3") (pin "15") (pinfunction "15_15") (pintype "passive"))
      (node (ref "R27") (pin "2") (pinfunction "2_2") (pintype "passive"))
    )
    (net (code "5") (name "/HIZ-") (class "Default")
      (node (ref "P3") (pin "14") (pinfunction "14_14") (pintype "passive"))
      (node (ref "R33") (pin "2") (pinfunction "2_2") (pintype "passive"))
    )
    (net (code "6") (name "/ILERI") (class "Default")
      (node (ref "P3") (pin "8") (pinfunction "8_8") (pintype "passive"))
      (node (ref "R16") (pin "2") (pinfunction "2_2") (pintype "passive"))
    )
    (net (code "7") (name "/IN_LINE") (class "Default")
      (node (ref "F1") (pin "1") (pinfunction "A_1") (pintype "passive"))
      (node (ref "R20") (pin "2") (pinfunction "B_2") (pintype "passive"))
      (node (ref "R35") (pin "2") (pinfunction "B_2") (pintype "passive"))
      (node (ref "R39") (pin "2") (pinfunction "B_2") (pintype "passive"))
      (node (ref "R41") (pin "2") (pinfunction "B_2") (pintype "passive"))
      (node (ref "T1") (pin "2") (pinfunction "A2_2") (pintype "passive"))
    )
    (net (code "8") (name "/ISITICI") (class "Default")
      (node (ref "P3") (pin "10") (pinfunction "10_10") (pintype "passive"))
      (node (ref "R38") (pin "1") (pinfunction "1_1") (pintype "passive"))
      (node (ref "R40") (pin "2") (pinfunction "2_2") (pintype "passive"))
    )
    (net (code "9") (name "/ISITICI_ON{slash}OFF") (class "Default")
      (node (ref "P3") (pin "5") (pinfunction "5_5") (pintype "passive"))
      (node (ref "R42") (pin "1") (pinfunction "1_1") (pintype "passive"))
    )
    (net (code "10") (name "/KO_A") (class "Default")
      (node (ref "KO") (pin "4") (pinfunction "P4_4") (pintype "passive"))
      (node (ref "P4") (pin "4") (pinfunction "4_4") (pintype "passive"))
    )
    (net (code "11") (name "/KO_D") (class "Default")
      (node (ref "KO") (pin "3") (pinfunction "P3_3") (pintype "passive"))
      (node (ref "P4") (pin "1") (pinfunction "1_1") (pintype "passive"))
      (node (ref "R18") (pin "2") (pinfunction "2_2") (pintype "passive"))
      (node (ref "R43") (pin "1") (pinfunction "1_1") (pintype "passive"))
    )
    (net (code "12") (name "/NOTR") (class "Default")
      (node (ref "KN2") (pin "1") (pinfunction "P1_1") (pintype "passive"))
      (node (ref "KN3") (pin "1") (pinfunction "P1_1") (pintype "passive"))
      (node (ref "R37") (pin "2") (pinfunction "B_2") (pintype "passive"))
    )
    (net (code "13") (name "/ROLE_1") (class "Default")
      (node (ref "P3") (pin "1") (pinfunction "1_1") (pintype "passive"))
      (node (ref "R5") (pin "1") (pinfunction "1_1") (pintype "passive"))
      (node (ref "R7") (pin "2") (pinfunction "2_2") (pintype "passive"))
    )
    (net (code "14") (name "/ROLE_2") (class "Default")
      (node (ref "P3") (pin "2") (pinfunction "2_2") (pintype "passive"))
      (node (ref "R12") (pin "1") (pinfunction "1_1") (pintype "passive"))
      (node (ref "R15") (pin "2") (pinfunction "2_2") (pintype "passive"))
    )
    (net (code "15") (name "/ROLE_3") (class "Default")
      (node (ref "P3") (pin "3") (pinfunction "3_3") (pintype "passive"))
      (node (ref "R22") (pin "1") (pinfunction "1_1") (pintype "passive"))
      (node (ref "R24") (pin "2") (pinfunction "2_2") (pintype "passive"))
    )
    (net (code "16") (name "/ROLL_PWM") (class "Default")
      (node (ref "P3") (pin "4") (pinfunction "4_4") (pintype "passive"))
      (node (ref "R28") (pin "1") (pinfunction "1_1") (pintype "passive"))
      (node (ref "R32") (pin "2") (pinfunction "2_2") (pintype "passive"))
    )
    (net (code "17") (name "/SCL") (class "Default")
      (node (ref "LCD") (pin "2") (pinfunction "P2_2") (pintype "passive"))
      (node (ref "P4") (pin "9") (pinfunction "9_9") (pintype "passive"))
    )
    (net (code "18") (name "/SDA") (class "Default")
      (node (ref "LCD") (pin "1") (pinfunction "P1_1") (pintype "passive"))
      (node (ref "P4") (pin "8") (pinfunction "8_8") (pintype "passive"))
    )
    (net (code "19") (name "/START") (class "Default")
      (node (ref "P3") (pin "6") (pinfunction "6_6") (pintype "passive"))
      (node (ref "R4") (pin "2") (pinfunction "2_2") (pintype "passive"))
    )
    (net (code "20") (name "/STOP") (class "Default")
      (node (ref "P3") (pin "7") (pinfunction "7_7") (pintype "passive"))
      (node (ref "R11") (pin "2") (pinfunction "2_2") (pintype "passive"))
    )
    (net (code "21") (name "/Zero_Cross") (class "Default")
      (node (ref "OP4") (pin "4") (pinfunction "C_4") (pintype "passive"))
      (node (ref "P3") (pin "11") (pinfunction "11_11") (pintype "passive"))
      (node (ref "R34") (pin "2") (pinfunction "2_2") (pintype "passive"))
    )
    (net (code "22") (name "GND") (class "Default")
      (node (ref "C1") (pin "1") (pinfunction "1_1") (pintype "passive"))
      (node (ref "C2") (pin "1") (pinfunction "1_1") (pintype "passive"))
      (node (ref "C3") (pin "1") (pinfunction "1_1") (pintype "passive"))
      (node (ref "C4") (pin "1") (pinfunction "1_1") (pintype "passive"))
      (node (ref "C5") (pin "1") (pinfunction "1_1") (pintype "passive"))
      (node (ref "C6") (pin "1") (pinfunction "1_1") (pintype "passive"))
      (node (ref "C7") (pin "1") (pinfunction "1_1") (pintype "passive"))
      (node (ref "GERI") (pin "1") (pinfunction "1_1") (pintype "passive"))
      (node (ref "HIZ+") (pin "1") (pinfunction "1_1") (pintype "passive"))
      (node (ref "HIZ-") (pin "1") (pinfunction "1_1") (pintype "passive"))
      (node (ref "ILERI") (pin "1") (pinfunction "1_1") (pintype "passive"))
      (node (ref "ISITICI") (pin "1") (pinfunction "1_1") (pintype "passive"))
      (node (ref "KO") (pin "2") (pinfunction "P2_2") (pintype "passive"))
      (node (ref "LCD") (pin "4") (pinfunction "P4_4") (pintype "passive"))
      (node (ref "LD1") (pin "1") (pinfunction "K_1") (pintype "passive"))
      (node (ref "LD2") (pin "1") (pinfunction "K_1") (pintype "passive"))
      (node (ref "LD3") (pin "1") (pinfunction "K_1") (pintype "passive"))
      (node (ref "LD4") (pin "1") (pinfunction "K_1") (pintype "passive"))
      (node (ref "LD5") (pin "1") (pinfunction "K_1") (pintype "passive"))
      (node (ref "LD6") (pin "1") (pinfunction "K_1") (pintype "passive"))
      (node (ref "LD7") (pin "1") (pinfunction "K_1") (pintype "passive"))
      (node (ref "OP1") (pin "2") (pinfunction "K_2") (pintype "passive"))
      (node (ref "OP2") (pin "2") (pinfunction "K_2") (pintype "passive"))
      (node (ref "OP3") (pin "2") (pinfunction "K_2") (pintype "passive"))
      (node (ref "OP4") (pin "3") (pinfunction "E_3") (pintype "passive"))
      (node (ref "OP5") (pin "2") (pinfunction "K_2") (pintype "passive"))
      (node (ref "OPT1") (pin "2") (pinfunction "K_2") (pintype "passive"))
      (node (ref "P3") (pin "12") (pinfunction "12_12") (pintype "passive"))
      (node (ref "P4") (pin "14") (pinfunction "14_14") (pintype "passive"))
      (node (ref "POWER") (pin "2") (pinfunction "2_2") (pintype "passive"))
      (node (ref "Q1") (pin "2") (pinfunction "E_2") (pintype "passive"))
      (node (ref "Q2") (pin "2") (pinfunction "E_2") (pintype "passive"))
      (node (ref "Q3") (pin "2") (pinfunction "E_2") (pintype "passive"))
      (node (ref "R17") (pin "1") (pinfunction "1_1") (pintype "passive"))
      (node (ref "R25") (pin "1") (pinfunction "1_1") (pintype "passive"))
      (node (ref "R43") (pin "2") (pinfunction "2_2") (pintype "passive"))
      (node (ref "R9") (pin "1") (pinfunction "1_1") (pintype "passive"))
      (node (ref "START") (pin "1") (pinfunction "1_1") (pintype "passive"))
      (node (ref "STOP") (pin "1") (pinfunction "1_1") (pintype "passive"))
    )
    (net (code "23") (name "Net-(BR1-A)") (class "Default")
      (node (ref "BR1") (pin "4") (pinfunction "A_4") (pintype "passive"))
      (node (ref "OP4") (pin "2") (pinfunction "K_2") (pintype "passive"))
    )
    (net (code "24") (name "Net-(BR1-K)") (class "Default")
      (node (ref "BR1") (pin "3") (pinfunction "K_3") (pintype "passive"))
      (node (ref "R36") (pin "1") (pinfunction "1_1") (pintype "passive"))
    )
    (net (code "25") (name "Net-(C1-Pad2)") (class "Default")
      (node (ref "C1") (pin "2") (pinfunction "2_2") (pintype "passive"))
      (node (ref "R3") (pin "1") (pinfunction "1_1") (pintype "passive"))
      (node (ref "R4") (pin "1") (pinfunction "1_1") (pintype "passive"))
      (node (ref "START") (pin "2") (pinfunction "2_2") (pintype "passive"))
    )
    (net (code "26") (name "Net-(C2-Pad2)") (class "Default")
      (node (ref "C2") (pin "2") (pinfunction "2_2") (pintype "passive"))
      (node (ref "ISITICI") (pin "2") (pinfunction "2_2") (pintype "passive"))
      (node (ref "R42") (pin "2") (pinfunction "2_2") (pintype "passive"))
      (node (ref "R8") (pin "1") (pinfunction "1_1") (pintype "passive"))
    )
    (net (code "27") (name "Net-(C3-Pad2)") (class "Default")
      (node (ref "C3") (pin "2") (pinfunction "2_2") (pintype "passive"))
      (node (ref "R10") (pin "1") (pinfunction "1_1") (pintype "passive"))
      (node (ref "R11") (pin "1") (pinfunction "1_1") (pintype "passive"))
      (node (ref "STOP") (pin "2") (pinfunction "2_2") (pintype "passive"))
    )
    (net (code "28") (name "Net-(C4-Pad2)") (class "Default")
      (node (ref "C4") (pin "2") (pinfunction "2_2") (pintype "passive"))
      (node (ref "ILERI") (pin "2") (pinfunction "2_2") (pintype "passive"))
      (node (ref "R13") (pin "1") (pinfunction "1_1") (pintype "passive"))
      (node (ref "R16") (pin "1") (pinfunction "1_1") (pintype "passive"))
    )
    (net (code "29") (name "Net-(C5-Pad2)") (class "Default")
      (node (ref "C5") (pin "2") (pinfunction "2_2") (pintype "passive"))
      (node (ref "GERI") (pin "2") (pinfunction "2_2") (pintype "passive"))
      (node (ref "R19") (pin "1") (pinfunction "1_1") (pintype "passive"))
      (node (ref "R21") (pin "1") (pinfunction "1_1") (pintype "passive"))
    )
    (net (code "30") (name "Net-(C6-Pad2)") (class "Default")
      (node (ref "C6") (pin "2") (pinfunction "2_2") (pintype "passive"))
      (node (ref "HIZ+") (pin "2") (pinfunction "2_2") (pintype "passive"))
      (node (ref "R26") (pin "1") (pinfunction "1_1") (pintype "passive"))
      (node (ref "R27") (pin "1") (pinfunction "1_1") (pintype "passive"))
    )
    (net (code "31") (name "Net-(C7-Pad2)") (class "Default")
      (node (ref "C7") (pin "2") (pinfunction "2_2") (pintype "passive"))
      (node (ref "HIZ-") (pin "2") (pinfunction "2_2") (pintype "passive"))
      (node (ref "R31") (pin "1") (pinfunction "1_1") (pintype "passive"))
      (node (ref "R33") (pin "1") (pinfunction "1_1") (pintype "passive"))
    )
    (net (code "32") (name "Net-(D1-A)") (class "Default")
      (node (ref "D1") (pin "2") (pinfunction "A_2") (pintype "passive"))
      (node (ref "Q1") (pin "3") (pinfunction "C_3") (pintype "passive"))
      (node (ref "RL1") (pin "2") (pinfunction "L1_2") (pintype "passive"))
    )
    (net (code "33") (name "Net-(D2-A)") (class "Default")
      (node (ref "D2") (pin "2") (pinfunction "A_2") (pintype "passive"))
      (node (ref "Q2") (pin "3") (pinfunction "C_3") (pintype "passive"))
      (node (ref "RL2") (pin "2") (pinfunction "L1_2") (pintype "passive"))
    )
    (net (code "34") (name "Net-(D3-A)") (class "Default")
      (node (ref "D3") (pin "2") (pinfunction "A_2") (pintype "passive"))
      (node (ref "Q3") (pin "3") (pinfunction "C_3") (pintype "passive"))
      (node (ref "RL3") (pin "2") (pinfunction "L1_2") (pintype "passive"))
    )
    (net (code "35") (name "Net-(F1-B)") (class "Default")
      (node (ref "F1") (pin "2") (pinfunction "B_2") (pintype "passive"))
      (node (ref "KN1") (pin "1") (pinfunction "P1_1") (pintype "passive"))
    )
    (net (code "36") (name "Net-(F2-A)") (class "Default")
      (node (ref "C8") (pin "1") (pinfunction "1_1") (pintype "passive"))
      (node (ref "F2") (pin "1") (pinfunction "A_1") (pintype "passive"))
      (node (ref "T1") (pin "1") (pinfunction "A1_1") (pintype "passive"))
    )
    (net (code "37") (name "Net-(F2-B)") (class "Default")
      (node (ref "F2") (pin "2") (pinfunction "B_2") (pintype "passive"))
      (node (ref "KN4") (pin "1") (pinfunction "P1_1") (pintype "passive"))
    )
    (net (code "38") (name "Net-(LD1-A)") (class "Default")
      (node (ref "LD1") (pin "2") (pinfunction "A_2") (pintype "passive"))
      (node (ref "R1") (pin "1") (pinfunction "1_1") (pintype "passive"))
    )
    (net (code "39") (name "Net-(LD2-A)") (class "Default")
      (node (ref "LD2") (pin "2") (pinfunction "A_2") (pintype "passive"))
      (node (ref "R2") (pin "1") (pinfunction "1_1") (pintype "passive"))
    )
    (net (code "40") (name "Net-(LD3-A)") (class "Default")
      (node (ref "LD3") (pin "2") (pinfunction "A_2") (pintype "passive"))
      (node (ref "R7") (pin "1") (pinfunction "1_1") (pintype "passive"))
    )
    (net (code "41") (name "Net-(LD4-A)") (class "Default")
      (node (ref "LD4") (pin "2") (pinfunction "A_2") (pintype "passive"))
      (node (ref "R15") (pin "1") (pinfunction "1_1") (pintype "passive"))
    )
    (net (code "42") (name "Net-(LD5-A)") (class "Default")
      (node (ref "LD5") (pin "2") (pinfunction "A_2") (pintype "passive"))
      (node (ref "R24") (pin "1") (pinfunction "1_1") (pintype "passive"))
    )
    (net (code "43") (name "Net-(LD6-A)") (class "Default")
      (node (ref "LD6") (pin "2") (pinfunction "A_2") (pintype "passive"))
      (node (ref "R32") (pin "1") (pinfunction "1_1") (pintype "passive"))
    )
    (net (code "44") (name "Net-(LD7-A)") (class "Default")
      (node (ref "LD7") (pin "2") (pinfunction "A_2") (pintype "passive"))
      (node (ref "R40") (pin "1") (pinfunction "1_1") (pintype "passive"))
    )
    (net (code "45") (name "Net-(OP1-A)") (class "Default")
      (node (ref "OP1") (pin "1") (pinfunction "A_1") (pintype "passive"))
      (node (ref "R5") (pin "2") (pinfunction "2_2") (pintype "passive"))
    )
    (net (code "46") (name "Net-(OP1-E)") (class "Default")
      (node (ref "OP1") (pin "3") (pinfunction "E_3") (pintype "passive"))
      (node (ref "R6") (pin "1") (pinfunction "1_1") (pintype "passive"))
      (node (ref "R9") (pin "2") (pinfunction "2_2") (pintype "passive"))
    )
    (net (code "47") (name "Net-(OP2-A)") (class "Default")
      (node (ref "OP2") (pin "1") (pinfunction "A_1") (pintype "passive"))
      (node (ref "R12") (pin "2") (pinfunction "2_2") (pintype "passive"))
    )
    (net (code "48") (name "Net-(OP2-E)") (class "Default")
      (node (ref "OP2") (pin "3") (pinfunction "E_3") (pintype "passive"))
      (node (ref "R14") (pin "1") (pinfunction "1_1") (pintype "passive"))
      (node (ref "R17") (pin "2") (pinfunction "2_2") (pintype "passive"))
    )
    (net (code "49") (name "Net-(OP3-A)") (class "Default")
      (node (ref "OP3") (pin "1") (pinfunction "A_1") (pintype "passive"))
      (node (ref "R22") (pin "2") (pinfunction "2_2") (pintype "passive"))
    )
    (net (code "50") (name "Net-(OP3-E)") (class "Default")
      (node (ref "OP3") (pin "3") (pinfunction "E_3") (pintype "passive"))
      (node (ref "R23") (pin "1") (pinfunction "1_1") (pintype "passive"))
      (node (ref "R25") (pin "2") (pinfunction "2_2") (pintype "passive"))
    )
    (net (code "51") (name "Net-(OP4-A)") (class "Default")
      (node (ref "OP4") (pin "1") (pinfunction "A_1") (pintype "passive"))
      (node (ref "R36") (pin "2") (pinfunction "2_2") (pintype "passive"))
    )
    (net (code "52") (name "Net-(OP5-A)") (class "Default")
      (node (ref "OP5") (pin "1") (pinfunction "A_1") (pintype "passive"))
      (node (ref "R38") (pin "2") (pinfunction "2_2") (pintype "passive"))
    )
    (net (code "53") (name "Net-(OP5-C)") (class "Default")
      (node (ref "OP5") (pin "6") (pinfunction "C_6") (pintype "passive"))
      (node (ref "R39") (pin "1") (pinfunction "A_1") (pintype "passive"))
    )
    (net (code "54") (name "Net-(OP5-E)") (class "Default")
      (node (ref "OP5") (pin "4") (pinfunction "E_4") (pintype "passive"))
      (node (ref "T1") (pin "3") (pinfunction "G_3") (pintype "passive"))
    )
    (net (code "55") (name "Net-(OPT1-A)") (class "Default")
      (node (ref "OPT1") (pin "1") (pinfunction "A_1") (pintype "passive"))
      (node (ref "R28") (pin "2") (pinfunction "2_2") (pintype "passive"))
    )
    (net (code "56") (name "Net-(OPT1-C)") (class "Default")
      (node (ref "OPT1") (pin "4") (pinfunction "C_4") (pintype "passive"))
      (node (ref "P6") (pin "1") (pinfunction "1_1") (pintype "passive"))
    )
    (net (code "57") (name "Net-(OPT1-E)") (class "Default")
      (node (ref "OPT1") (pin "3") (pinfunction "E_3") (pintype "passive"))
      (node (ref "R29") (pin "1") (pinfunction "A_1") (pintype "passive"))
    )
    (net (code "58") (name "Net-(P4-Pad5)") (class "Default")
      (node (ref "P4") (pin "5") (pinfunction "5_5") (pintype "passive"))
      (node (ref "TP2") (pin "1") (pinfunction "1_1") (pintype "passive"))
    )
    (net (code "59") (name "Net-(P4-Pad6)") (class "Default")
      (node (ref "P4") (pin "6") (pinfunction "6_6") (pintype "passive"))
      (node (ref "TP1") (pin "1") (pinfunction "1_1") (pintype "passive"))
    )
    (net (code "60") (name "Net-(P4-Pad7)") (class "Default")
      (node (ref "P4") (pin "7") (pinfunction "7_7") (pintype "passive"))
      (node (ref "TP3") (pin "1") (pinfunction "1_1") (pintype "passive"))
    )
    (net (code "61") (name "Net-(P4-Pad10)") (class "Default")
      (node (ref "P4") (pin "10") (pinfunction "10_10") (pintype "passive"))
      (node (ref "TP4") (pin "1") (pinfunction "1_1") (pintype "passive"))
    )
    (net (code "62") (name "Net-(P4-Pad11)") (class "Default")
      (node (ref "P4") (pin "11") (pinfunction "11_11") (pintype "passive"))
      (node (ref "TP5") (pin "1") (pinfunction "1_1") (pintype "passive"))
    )
    (net (code "63") (name "Net-(Q1-B)") (class "Default")
      (node (ref "Q1") (pin "1") (pinfunction "B_1") (pintype "passive"))
      (node (ref "R6") (pin "2") (pinfunction "2_2") (pintype "passive"))
    )
    (net (code "64") (name "Net-(Q2-B)") (class "Default")
      (node (ref "Q2") (pin "1") (pinfunction "B_1") (pintype "passive"))
      (node (ref "R14") (pin "2") (pinfunction "2_2") (pintype "passive"))
    )
    (net (code "65") (name "Net-(Q3-B)") (class "Default")
      (node (ref "Q3") (pin "1") (pinfunction "B_1") (pintype "passive"))
      (node (ref "R23") (pin "2") (pinfunction "2_2") (pintype "passive"))
    )
    (net (code "66") (name "Net-(R20-A)") (class "Default")
      (node (ref "BR1") (pin "1") (pinfunction "C_1") (pintype "passive"))
      (node (ref "R20") (pin "1") (pinfunction "A_1") (pintype "passive"))
      (node (ref "R35") (pin "1") (pinfunction "A_1") (pintype "passive"))
    )
    (net (code "67") (name "Net-(R29-B)") (class "Default")
      (node (ref "P6") (pin "2") (pinfunction "2_2") (pintype "passive"))
      (node (ref "R29") (pin "2") (pinfunction "B_2") (pintype "passive"))
      (node (ref "R30") (pin "1") (pinfunction "A_1") (pintype "passive"))
    )
    (net (code "68") (name "Net-(R30-B)") (class "Default")
      (node (ref "P6") (pin "3") (pinfunction "3_3") (pintype "passive"))
      (node (ref "R30") (pin "2") (pinfunction "B_2") (pintype "passive"))
    )
    (net (code "69") (name "Net-(R37-A)") (class "Default")
      (node (ref "BR1") (pin "2") (pinfunction "C_2") (pintype "passive"))
      (node (ref "R37") (pin "1") (pinfunction "A_1") (pintype "passive"))
    )
    (net (code "70") (name "Net-(R41-A)") (class "Default")
      (node (ref "C8") (pin "2") (pinfunction "2_2") (pintype "passive"))
      (node (ref "R41") (pin "1") (pinfunction "A_1") (pintype "passive"))
    )
    (net (code "71") (name "Net-(RL1-C)") (class "Default")
      (node (ref "P1") (pin "2") (pinfunction "2_2") (pintype "passive"))
      (node (ref "RL1") (pin "1") (pinfunction "C_1") (pintype "passive"))
    )
    (net (code "72") (name "Net-(RL1-NC)") (class "Default")
      (node (ref "P1") (pin "1") (pinfunction "1_1") (pintype "passive"))
      (node (ref "RL1") (pin "4") (pinfunction "NC_4") (pintype "passive"))
    )
    (net (code "73") (name "Net-(RL1-NO)") (class "Default")
      (node (ref "P1") (pin "3") (pinfunction "3_3") (pintype "passive"))
      (node (ref "RL1") (pin "3") (pinfunction "NO_3") (pintype "passive"))
    )
    (net (code "74") (name "Net-(RL2-C)") (class "Default")
      (node (ref "P2") (pin "2") (pinfunction "2_2") (pintype "passive"))
      (node (ref "RL2") (pin "1") (pinfunction "C_1") (pintype "passive"))
    )
    (net (code "75") (name "Net-(RL2-NC)") (class "Default")
      (node (ref "P2") (pin "1") (pinfunction "1_1") (pintype "passive"))
      (node (ref "RL2") (pin "4") (pinfunction "NC_4") (pintype "passive"))
    )
    (net (code "76") (name "Net-(RL2-NO)") (class "Default")
      (node (ref "P2") (pin "3") (pinfunction "3_3") (pintype "passive"))
      (node (ref "RL2") (pin "3") (pinfunction "NO_3") (pintype "passive"))
    )
    (net (code "77") (name "Net-(RL3-C)") (class "Default")
      (node (ref "P5") (pin "2") (pinfunction "2_2") (pintype "passive"))
      (node (ref "RL3") (pin "1") (pinfunction "C_1") (pintype "passive"))
    )
    (net (code "78") (name "Net-(RL3-NC)") (class "Default")
      (node (ref "P5") (pin "1") (pinfunction "1_1") (pintype "passive"))
      (node (ref "RL3") (pin "4") (pinfunction "NC_4") (pintype "passive"))
    )
    (net (code "79") (name "Net-(RL3-NO)") (class "Default")
      (node (ref "P5") (pin "3") (pinfunction "3_3") (pintype "passive"))
      (node (ref "RL3") (pin "3") (pinfunction "NO_3") (pintype "passive"))
    )
    (net (code "80") (name "VIN") (class "Default")
      (node (ref "P4") (pin "15") (pinfunction "15_15") (pintype "passive"))
      (node (ref "POWER") (pin "1") (pinfunction "1_1") (pintype "passive"))
      (node (ref "R2") (pin "2") (pinfunction "2_2") (pintype "passive"))
    )
    (net (code "81") (name "unconnected-(P3-Pad13)") (class "Default")
      (node (ref "P3") (pin "13") (pinfunction "13_13") (pintype "passive+no_connect"))
    )
    (net (code "82") (name "unconnected-(P4-Pad3)") (class "Default")
      (node (ref "P4") (pin "3") (pinfunction "3_3") (pintype "passive+no_connect"))
    )
    (net (code "83") (name "unconnected-(P4-Pad13)") (class "Default")
      (node (ref "P4") (pin "13") (pinfunction "13_13") (pintype "passive+no_connect"))
    )
    (net (code "84") (name "unconnected-(VD1-Pad0)") (class "Default")
      (node (ref "VD1") (pin "0") (pinfunction "0_0") (pintype "passive+no_connect"))
    )
    (net (code "85") (name "unconnected-(VD2-Pad0)") (class "Default")
      (node (ref "VD2") (pin "0") (pinfunction "0_0") (pintype "passive+no_connect"))
    )
    (net (code "86") (name "unconnected-(VD3-Pad0)") (class "Default")
      (node (ref "VD3") (pin "0") (pinfunction "0_0") (pintype "passive+no_connect"))
    )
    (net (code "87") (name "unconnected-(VD4-Pad0)") (class "Default")
      (node (ref "VD4") (pin "0") (pinfunction "0_0") (pintype "passive+no_connect"))
    )
  )
)
